# design.net
KiCad netlist of a schematic drawn in Altium Designer
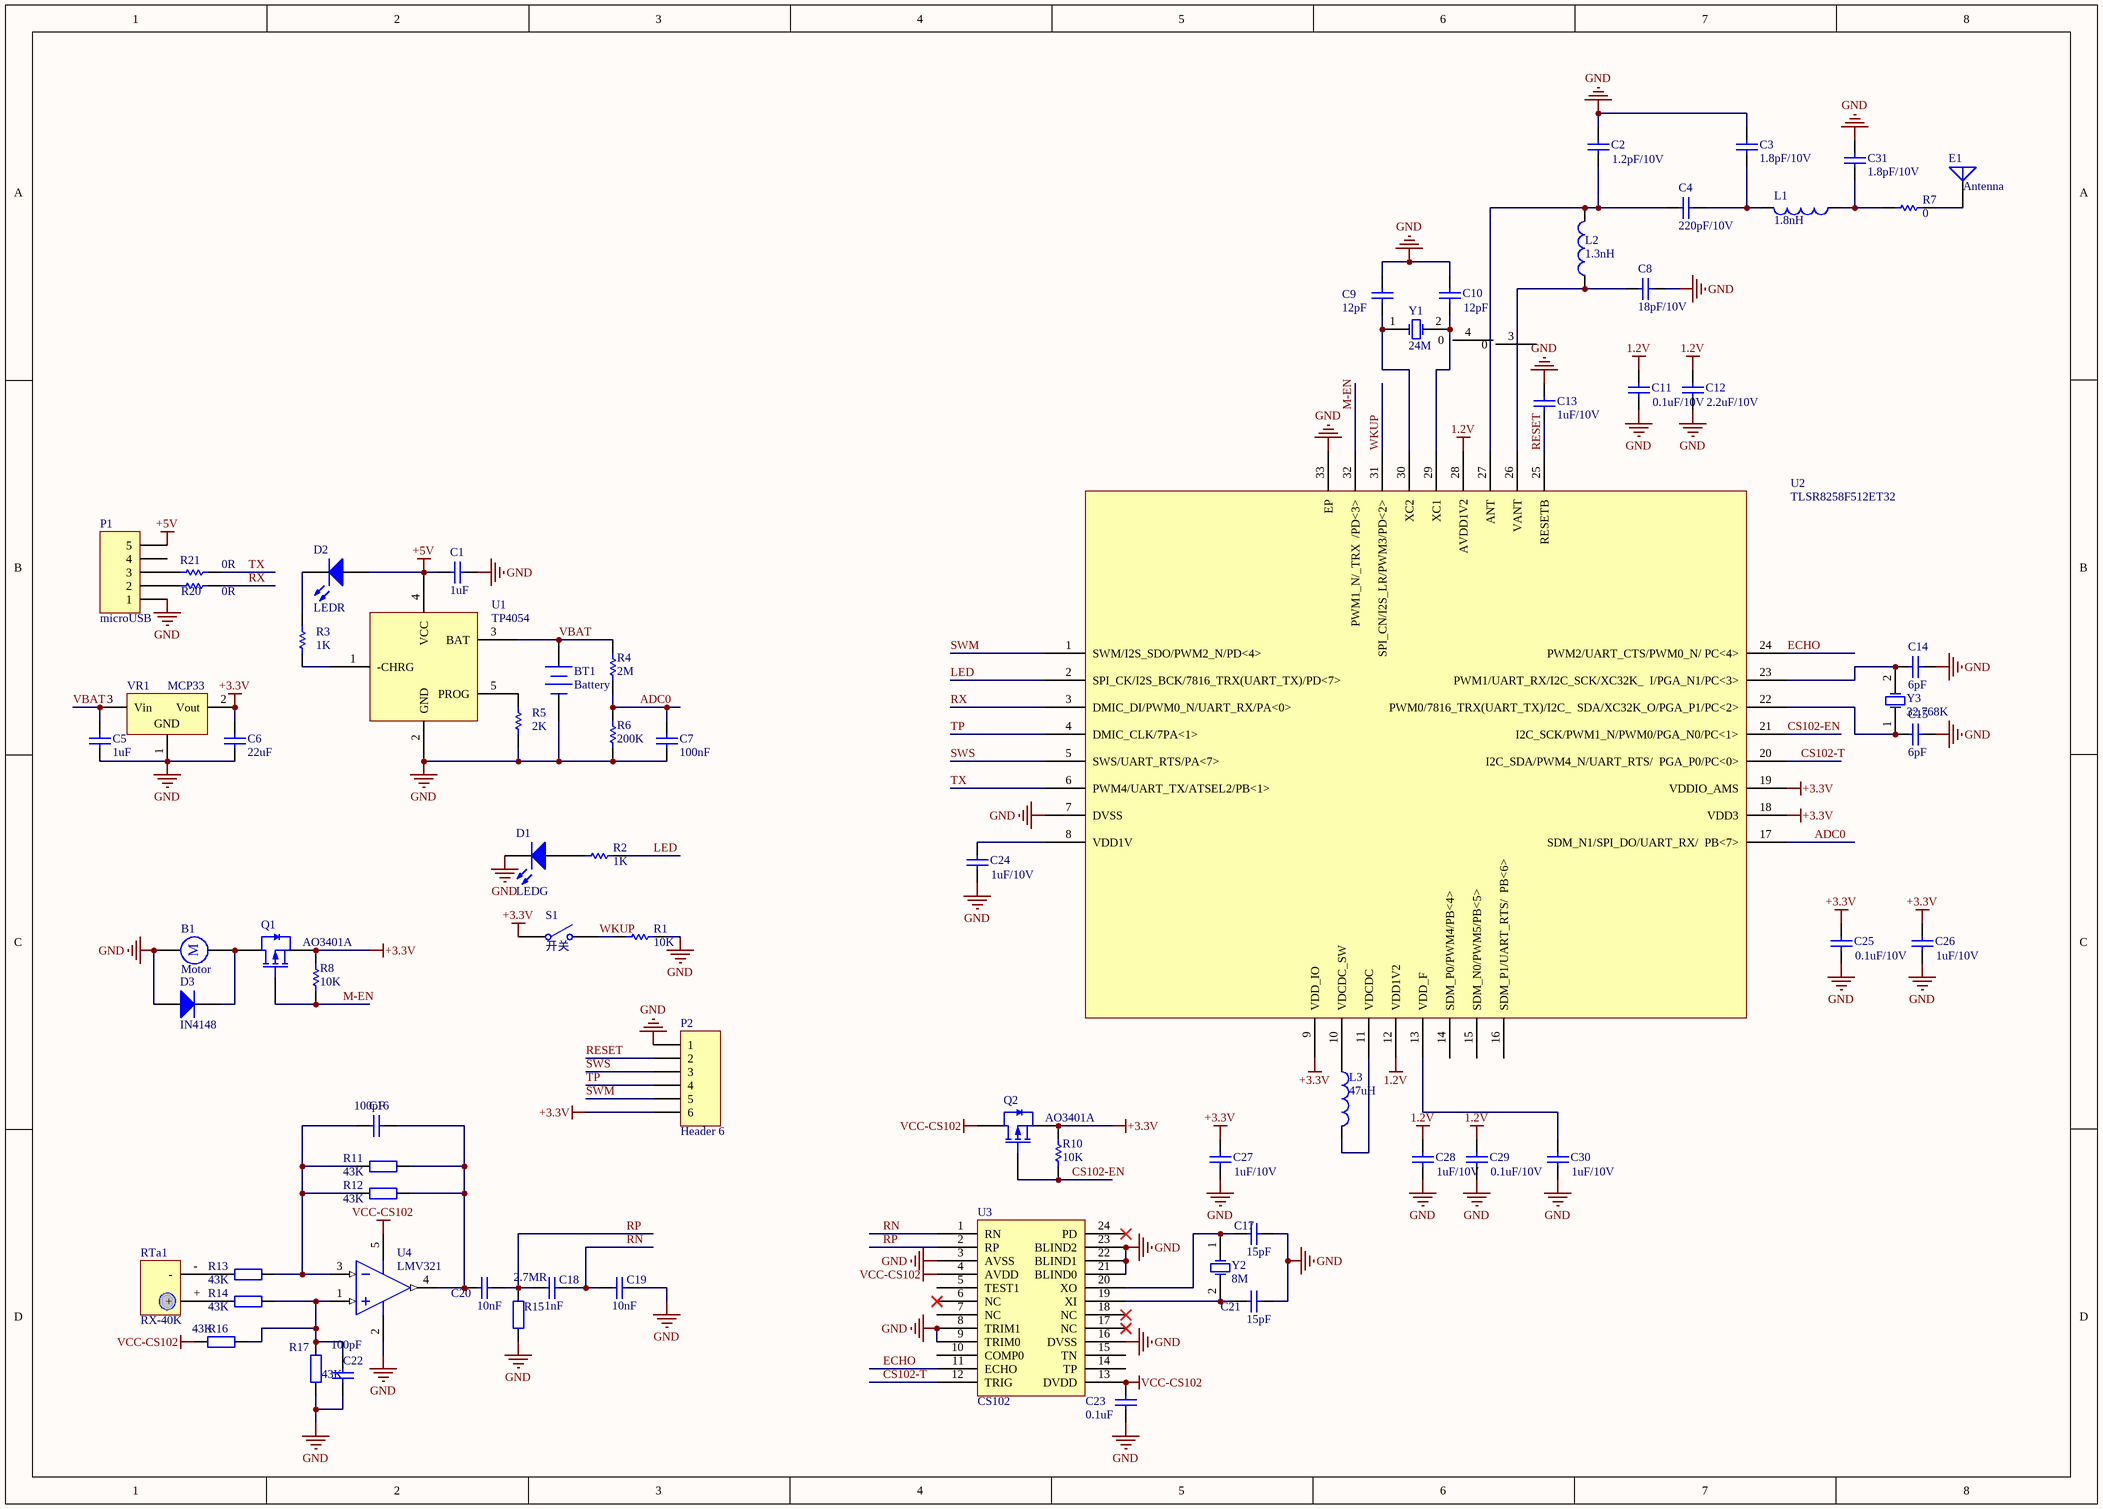
[diagram p0: 接收端原理图.SchDoc]

(export (version "E")
  (design (tool "Eeschema 10.0.6"))
  (components
    (comp (ref "B1")
      (value "Motor")
      (footprint "MOTO-40*44*114 - 3D")
      (description "Motor, General Kind")
      (fields (field (name "PUBLISHER") "Altium Limited"))
      (libsource (lib "Miscellaneous Devices") (part "Motor"))
    )
    (comp (ref "BT1")
      (value "Battery")
      (footprint "BT")
      (description "Multicell Battery")
      (fields (field (name "PUBLISHER") "Altium Limited"))
      (libsource (lib "Miscellaneous Devices") (part "Battery"))
    )
    (comp (ref "C1")
      (value "1uF")
      (description "Capacitor")
      (fields (field (name "PUBLISHER") "Altium Limited"))
      (libsource (lib "Miscellaneous Devices") (part "Cap"))
    )
    (comp (ref "C2")
      (value "1.2pF/10V")
      (footprint "0402")
      (description "Capacitor")
      (fields (field (name "PUBLISHER") "Altium Limited"))
      (libsource (lib "Miscellaneous Devices") (part "Cap"))
    )
    (comp (ref "C3")
      (value "1.8pF/10V")
      (footprint "0402")
      (description "Capacitor")
      (fields (field (name "PUBLISHER") "Altium Limited"))
      (libsource (lib "Miscellaneous Devices") (part "Cap"))
    )
    (comp (ref "C4")
      (value "220pF/10V")
      (footprint "0402")
      (description "Capacitor")
      (fields (field (name "PUBLISHER") "Altium Limited"))
      (libsource (lib "Miscellaneous Devices") (part "Cap"))
    )
    (comp (ref "C5")
      (value "1uF")
      (description "Capacitor")
      (fields (field (name "PUBLISHER") "Altium Limited"))
      (libsource (lib "Miscellaneous Devices") (part "Cap"))
    )
    (comp (ref "C6")
      (value "22uF")
      (description "Capacitor")
      (fields (field (name "PUBLISHER") "Altium Limited"))
      (libsource (lib "Miscellaneous Devices") (part "Cap"))
    )
    (comp (ref "C7")
      (value "100nF")
      (description "Capacitor")
      (fields (field (name "PUBLISHER") "Altium Limited"))
      (libsource (lib "Miscellaneous Devices") (part "Cap"))
    )
    (comp (ref "C8")
      (value "18pF/10V")
      (footprint "0402")
      (description "Capacitor")
      (fields (field (name "PUBLISHER") "Altium Limited"))
      (libsource (lib "Miscellaneous Devices") (part "Cap"))
    )
    (comp (ref "C9")
      (value "12pF")
      (footprint "0402")
      (description "Capacitor")
      (fields (field (name "PUBLISHER") "Altium Limited"))
      (libsource (lib "Miscellaneous Devices") (part "Cap"))
    )
    (comp (ref "C10")
      (value "12pF")
      (footprint "0402")
      (description "Capacitor")
      (fields (field (name "PUBLISHER") "Altium Limited"))
      (libsource (lib "Miscellaneous Devices") (part "Cap"))
    )
    (comp (ref "C11")
      (value "0.1uF/10V")
      (footprint "0402")
      (description "Capacitor")
      (fields (field (name "PUBLISHER") "Altium Limited"))
      (libsource (lib "Miscellaneous Devices") (part "Cap"))
    )
    (comp (ref "C12")
      (value "2.2uF/10V")
      (footprint "0402")
      (description "Capacitor")
      (fields (field (name "PUBLISHER") "Altium Limited"))
      (libsource (lib "Miscellaneous Devices") (part "Cap"))
    )
    (comp (ref "C13")
      (value "1uF/10V")
      (footprint "0402")
      (description "Capacitor")
      (fields (field (name "PUBLISHER") "Altium Limited"))
      (libsource (lib "Miscellaneous Devices") (part "Cap"))
    )
    (comp (ref "C14")
      (value "6pF")
      (footprint "0402")
      (description "Capacitor")
      (fields (field (name "PUBLISHER") "Altium Limited"))
      (libsource (lib "Miscellaneous Devices") (part "Cap"))
    )
    (comp (ref "C15")
      (value "6pF")
      (footprint "0402")
      (description "Capacitor")
      (fields (field (name "PUBLISHER") "Altium Limited"))
      (libsource (lib "Miscellaneous Devices") (part "Cap"))
    )
    (comp (ref "C16")
      (value "100pF")
      (footprint "0402")
      (description "Capacitor")
      (fields (field (name "PUBLISHER") "Altium Limited"))
      (libsource (lib "Miscellaneous Devices") (part "Cap"))
    )
    (comp (ref "C17")
      (value "15pF")
      (footprint "0402")
      (description "Capacitor")
      (fields (field (name "PUBLISHER") "Altium Limited"))
      (libsource (lib "Miscellaneous Devices") (part "Cap"))
    )
    (comp (ref "C18")
      (value "1nF")
      (footprint "0402")
      (description "Capacitor")
      (fields (field (name "PUBLISHER") "Altium Limited"))
      (libsource (lib "Miscellaneous Devices") (part "Cap"))
    )
    (comp (ref "C19")
      (value "10nF")
      (footprint "0402")
      (description "Capacitor")
      (fields (field (name "PUBLISHER") "Altium Limited"))
      (libsource (lib "Miscellaneous Devices") (part "Cap"))
    )
    (comp (ref "C20")
      (value "10nF")
      (footprint "0402")
      (description "Capacitor")
      (fields (field (name "PUBLISHER") "Altium Limited"))
      (libsource (lib "Miscellaneous Devices") (part "Cap"))
    )
    (comp (ref "C21")
      (value "15pF")
      (footprint "0402")
      (description "Capacitor")
      (fields (field (name "PUBLISHER") "Altium Limited"))
      (libsource (lib "Miscellaneous Devices") (part "Cap"))
    )
    (comp (ref "C22")
      (value "100pF")
      (footprint "0402")
      (description "Capacitor")
      (fields (field (name "PUBLISHER") "Altium Limited"))
      (libsource (lib "Miscellaneous Devices") (part "Cap"))
    )
    (comp (ref "C23")
      (value "0.1uF")
      (description "Capacitor")
      (fields (field (name "PUBLISHER") "Altium Limited"))
      (libsource (lib "Miscellaneous Devices") (part "Cap"))
    )
    (comp (ref "C24")
      (value "1uF/10V")
      (footprint "0402")
      (description "Capacitor")
      (fields (field (name "PUBLISHER") "Altium Limited"))
      (libsource (lib "Miscellaneous Devices") (part "Cap"))
    )
    (comp (ref "C25")
      (value "0.1uF/10V")
      (footprint "0402")
      (description "Capacitor")
      (fields (field (name "PUBLISHER") "Altium Limited"))
      (libsource (lib "Miscellaneous Devices") (part "Cap"))
    )
    (comp (ref "C26")
      (value "1uF/10V")
      (footprint "0402")
      (description "Capacitor")
      (fields (field (name "PUBLISHER") "Altium Limited"))
      (libsource (lib "Miscellaneous Devices") (part "Cap"))
    )
    (comp (ref "C27")
      (value "1uF/10V")
      (footprint "0402")
      (description "Capacitor")
      (fields (field (name "PUBLISHER") "Altium Limited"))
      (libsource (lib "Miscellaneous Devices") (part "Cap"))
    )
    (comp (ref "C28")
      (value "1uF/10V")
      (footprint "0402")
      (description "Capacitor")
      (fields (field (name "PUBLISHER") "Altium Limited"))
      (libsource (lib "Miscellaneous Devices") (part "Cap"))
    )
    (comp (ref "C29")
      (value "0.1uF/10V")
      (footprint "0402")
      (description "Capacitor")
      (fields (field (name "PUBLISHER") "Altium Limited"))
      (libsource (lib "Miscellaneous Devices") (part "Cap"))
    )
    (comp (ref "C30")
      (value "1uF/10V")
      (footprint "0402")
      (description "Capacitor")
      (fields (field (name "PUBLISHER") "Altium Limited"))
      (libsource (lib "Miscellaneous Devices") (part "Cap"))
    )
    (comp (ref "C31")
      (value "1.8pF/10V")
      (footprint "0402")
      (description "Capacitor")
      (fields (field (name "PUBLISHER") "Altium Limited"))
      (libsource (lib "Miscellaneous Devices") (part "Cap"))
    )
    (comp (ref "D1")
      (value "LEDG")
      (footprint "LED0603")
      (description "Typical INFRARED GaAs LED")
      (fields (field (name "PUBLISHER") "Altium Limited"))
      (libsource (lib "Miscellaneous Devices") (part "LED0"))
    )
    (comp (ref "D2")
      (value "LEDR")
      (footprint "LED0603")
      (description "Typical INFRARED GaAs LED")
      (fields (field (name "PUBLISHER") "Altium Limited"))
      (libsource (lib "Miscellaneous Devices") (part "LED0"))
    )
    (comp (ref "D3")
      (value "IN4148")
      (footprint "LED0603")
      (description "Default Diode")
      (fields (field (name "PUBLISHER") "Altium Limited"))
      (libsource (lib "Miscellaneous Devices") (part "Diode"))
    )
    (comp (ref "E1")
      (value "Antenna")
      (footprint "AN3216")
      (description "Generic Antenna")
      (fields (field (name "PUBLISHER") "Altium Limited"))
      (libsource (lib "Miscellaneous Devices") (part "Antenna"))
    )
    (comp (ref "L1")
      (value "1.8nH")
      (description "Inductor")
      (fields (field (name "PUBLISHER") "Altium Limited"))
      (libsource (lib "Miscellaneous Devices") (part "Inductor"))
    )
    (comp (ref "L2")
      (value "1.3nH")
      (description "Inductor")
      (fields (field (name "PUBLISHER") "Altium Limited"))
      (libsource (lib "Miscellaneous Devices") (part "Inductor"))
    )
    (comp (ref "L3")
      (value "47uH")
      (description "Inductor")
      (fields (field (name "PUBLISHER") "Altium Limited"))
      (libsource (lib "Miscellaneous Devices") (part "Inductor"))
    )
    (comp (ref "P1")
      (value "microUSB")
      (footprint "MICROUSB")
      (description "Header, 5-Pin")
      (fields (field (name "PUBLISHER") "Altium Limited"))
      (libsource (lib "Miscellaneous Connectors") (part "Header 5"))
    )
    (comp (ref "P2")
      (value "Header 6")
      (footprint "SIP6-1.27")
      (description "Header, 6-Pin")
      (fields (field (name "PUBLISHER") "Altium Limited"))
      (libsource (lib "Miscellaneous Connectors") (part "Header 6"))
    )
    (comp (ref "Q1")
      (value "AO3401A")
      (footprint "AO3401")
      (description "MOS(场效应管)")
      (libsource (lib "Miscellaneous Devices LC") (part "AO3401A P道沟 X13A15 SOT-23"))
    )
    (comp (ref "Q2")
      (value "AO3401A")
      (footprint "SOT23")
      (description "MOS(场效应管)")
      (libsource (lib "Miscellaneous Devices LC") (part "AO3401A P道沟 X13A15 SOT-23"))
    )
    (comp (ref "R1")
      (value "10K")
      (description "Resistor")
      (fields (field (name "PUBLISHER") "Altium Limited"))
      (libsource (lib "Miscellaneous Devices") (part "Res1"))
    )
    (comp (ref "R2")
      (value "1K")
      (description "Resistor")
      (fields (field (name "PUBLISHER") "Altium Limited"))
      (libsource (lib "Miscellaneous Devices") (part "Res1"))
    )
    (comp (ref "R3")
      (value "1K")
      (description "Resistor")
      (fields (field (name "PUBLISHER") "Altium Limited"))
      (libsource (lib "Miscellaneous Devices") (part "Res1"))
    )
    (comp (ref "R4")
      (value "2M")
      (description "Resistor")
      (fields (field (name "PUBLISHER") "Altium Limited"))
      (libsource (lib "Miscellaneous Devices") (part "Res1"))
    )
    (comp (ref "R5")
      (value "2K")
      (description "Resistor")
      (fields (field (name "PUBLISHER") "Altium Limited"))
      (libsource (lib "Miscellaneous Devices") (part "Res1"))
    )
    (comp (ref "R6")
      (value "200K")
      (description "Resistor")
      (fields (field (name "PUBLISHER") "Altium Limited"))
      (libsource (lib "Miscellaneous Devices") (part "Res1"))
    )
    (comp (ref "R7")
      (value "0")
      (description "Resistor")
      (fields (field (name "PUBLISHER") "Altium Limited"))
      (libsource (lib "Miscellaneous Devices") (part "Res1"))
    )
    (comp (ref "R8")
      (value "10K")
      (description "Resistor")
      (fields (field (name "PUBLISHER") "Altium Limited"))
      (libsource (lib "Miscellaneous Devices") (part "Res1"))
    )
    (comp (ref "R10")
      (value "10K")
      (description "Resistor")
      (fields (field (name "PUBLISHER") "Altium Limited"))
      (libsource (lib "Miscellaneous Devices") (part "Res1"))
    )
    (comp (ref "R11")
      (value "43K")
      (footprint "0402")
      (description "Resistor")
      (fields (field (name "PUBLISHER") "Altium Limited"))
      (libsource (lib "") (part "Res2_1"))
    )
    (comp (ref "R12")
      (value "43K")
      (footprint "0402")
      (description "Resistor")
      (fields (field (name "PUBLISHER") "Altium Limited"))
      (libsource (lib "") (part "Res2_1"))
    )
    (comp (ref "R13")
      (value "43K")
      (footprint "0402")
      (description "Resistor")
      (fields (field (name "PUBLISHER") "Altium Limited"))
      (libsource (lib "") (part "Res2_1"))
    )
    (comp (ref "R14")
      (value "43K")
      (footprint "0402")
      (description "Resistor")
      (fields (field (name "PUBLISHER") "Altium Limited"))
      (libsource (lib "") (part "Res2_1"))
    )
    (comp (ref "R15")
      (value "2.7MR")
      (footprint "0402")
      (description "Resistor")
      (fields (field (name "PUBLISHER") "Altium Limited"))
      (libsource (lib "Miscellaneous Devices") (part "Res2"))
    )
    (comp (ref "R16")
      (value "43K")
      (footprint "0402")
      (description "Resistor")
      (fields (field (name "PUBLISHER") "Altium Limited"))
      (libsource (lib "") (part "Res2_2"))
    )
    (comp (ref "R17")
      (value "43K")
      (footprint "0402")
      (description "Resistor")
      (fields (field (name "PUBLISHER") "Altium Limited"))
      (libsource (lib "Miscellaneous Devices") (part "Res2"))
    )
    (comp (ref "R20")
      (value "0R")
      (description "Resistor")
      (fields (field (name "PUBLISHER") "Altium Limited"))
      (libsource (lib "Miscellaneous Devices") (part "Res1"))
    )
    (comp (ref "R21")
      (value "0R")
      (description "Resistor")
      (fields (field (name "PUBLISHER") "Altium Limited"))
      (libsource (lib "Miscellaneous Devices") (part "Res1"))
    )
    (comp (ref "RTa1") (value "RX-40K") (footprint "US-10mm") (libsource (lib "USLib") (part "TC40K")))
    (comp (ref "S1")
      (value "开关")
      (footprint "SW3x6x5")
      (description "Single-Pole, Single-Throw Switch")
      (fields (field (name "PUBLISHER") "Altium Limited"))
      (libsource (lib "Miscellaneous Devices") (part "SW-SPST"))
    )
    (comp (ref "U1") (value "TP4054") (footprint "TP4054") (libsource (lib "Schlib1") (part "TP4054")))
    (comp (ref "U2")
      (value "TLSR8258F512ET32")
      (footprint "QFN-32")
      (libsource (lib "stm32") (part "TLSR8258F512ET32"))
    )
    (comp (ref "U3") (value "CS102") (footprint "TSSOP24") (libsource (lib "USLib") (part "CS100")))
    (comp (ref "U4")
      (value "LMV321")
      (footprint "MF05A_N")
      (description "General Purpose, Low Voltage, Rail-to-Rail Output Operational Amplifiers")
      (fields
        (field (name "PARTNUMBER") "LMV321M5")
        (field (name "MANUFACTURER") "National Semiconductor")
        (field (name "PUBLISHER") "Altium Limited")
      )
      (libsource (lib "NSC Amplifier") (part "LMV321M5"))
    )
    (comp (ref "VR1")
      (value "MCP33")
      (footprint "SOT23")
      (description "Voltage Regulator")
      (fields (field (name "PUBLISHER") "Altium Limited"))
      (libsource (lib "Miscellaneous Devices") (part "Volt Reg"))
    )
    (comp (ref "Y1")
      (value "24M")
      (footprint "XTAL4TN_3225")
      (description "Crystal Oscillator")
      (fields (field (name "PUBLISHER") "Altium Limited"))
      (libsource (lib "Miscellaneous Devices") (part "XTAL"))
    )
    (comp (ref "Y2")
      (value "8M")
      (footprint "5032")
      (description "Crystal Oscillator")
      (fields (field (name "PUBLISHER") "Altium Limited"))
      (libsource (lib "") (part "XTAL_1"))
    )
    (comp (ref "Y3")
      (value "32.768K")
      (footprint "S3215")
      (description "Crystal Oscillator")
      (fields (field (name "PUBLISHER") "Altium Limited"))
      (libsource (lib "") (part "XTAL_1"))
    )
  )
  (nets
    (net (code "1") (name "+3.3V") (class "Default")
      (node (ref "C25") (pin "2") (pinfunction "2_2") (pintype "passive"))
      (node (ref "C26") (pin "2") (pinfunction "2_2") (pintype "passive"))
      (node (ref "C27") (pin "2") (pinfunction "2_2") (pintype "passive"))
      (node (ref "C6") (pin "1") (pinfunction "1_1") (pintype "passive"))
      (node (ref "P2") (pin "6") (pinfunction "6_6") (pintype "passive"))
      (node (ref "Q1") (pin "2") (pinfunction "S_2") (pintype "passive"))
      (node (ref "Q2") (pin "2") (pinfunction "S_2") (pintype "passive"))
      (node (ref "R10") (pin "2") (pinfunction "2_2") (pintype "passive"))
      (node (ref "R8") (pin "2") (pinfunction "2_2") (pintype "passive"))
      (node (ref "S1") (pin "1") (pinfunction "COMMON_1") (pintype "passive"))
      (node (ref "U2") (pin "18") (pinfunction "VDD3_18") (pintype "passive"))
      (node (ref "U2") (pin "19") (pinfunction "VDDIO_AMS_19") (pintype "passive"))
      (node (ref "U2") (pin "9") (pinfunction "VDD_IO_9") (pintype "passive"))
      (node (ref "VR1") (pin "2") (pinfunction "Vout_2") (pintype "passive"))
    )
    (net (code "2") (name "+5V") (class "Default")
      (node (ref "C1") (pin "2") (pinfunction "2_2") (pintype "passive"))
      (node (ref "D2") (pin "1") (pinfunction "A_1") (pintype "passive"))
      (node (ref "P1") (pin "5") (pinfunction "5_5") (pintype "passive"))
      (node (ref "U1") (pin "4") (pinfunction "VCC_4") (pintype "passive"))
    )
    (net (code "3") (name "/ADC0") (class "Default")
      (node (ref "C7") (pin "2") (pinfunction "2_2") (pintype "passive"))
      (node (ref "R4") (pin "1") (pinfunction "1_1") (pintype "passive"))
      (node (ref "R6") (pin "2") (pinfunction "2_2") (pintype "passive"))
      (node (ref "U2") (pin "17") (pinfunction "SDM_N1/SPI_DO/UART_RX/__PB<7>_17") (pintype "passive"))
    )
    (net (code "4") (name "/CS102-EN") (class "Default")
      (node (ref "Q2") (pin "1") (pinfunction "G_1") (pintype "passive"))
      (node (ref "R10") (pin "1") (pinfunction "1_1") (pintype "passive"))
      (node (ref "U2") (pin "21") (pinfunction "I2C_SCK/PWM1_N/PWM0/PGA_N0/PC<1>_21") (pintype "passive"))
    )
    (net (code "5") (name "/CS102-T") (class "Default")
      (node (ref "U2") (pin "20") (pinfunction "I2C_SDA/PWM4_N/UART_RTS/__PGA_P0/PC<0>_20") (pintype "passive"))
      (node (ref "U3") (pin "12") (pinfunction "TRIG_12") (pintype "passive"))
    )
    (net (code "6") (name "/ECHO") (class "Default")
      (node (ref "U2") (pin "24") (pinfunction "PWM2/UART_CTS/PWM0_N/_PC<4>_24") (pintype "passive"))
      (node (ref "U3") (pin "11") (pinfunction "ECHO_11") (pintype "passive"))
    )
    (net (code "7") (name "/LED") (class "Default")
      (node (ref "R2") (pin "1") (pinfunction "1_1") (pintype "passive"))
      (node (ref "U2") (pin "2") (pinfunction "SPI_CK/I2S_BCK/7816_TRX(UART_TX)/PD<7>_2") (pintype "passive"))
    )
    (net (code "8") (name "/M-EN") (class "Default")
      (node (ref "Q1") (pin "1") (pinfunction "G_1") (pintype "passive"))
      (node (ref "R8") (pin "1") (pinfunction "1_1") (pintype "passive"))
      (node (ref "U2") (pin "32") (pinfunction "PWM1_N/_TRX__/PD<3>_32") (pintype "passive"))
    )
    (net (code "9") (name "/RESET") (class "Default")
      (node (ref "C13") (pin "2") (pinfunction "2_2") (pintype "passive"))
      (node (ref "P2") (pin "2") (pinfunction "2_2") (pintype "passive"))
      (node (ref "U2") (pin "25") (pinfunction "RESETB_25") (pintype "passive"))
    )
    (net (code "10") (name "/RN") (class "Default")
      (node (ref "C18") (pin "2") (pinfunction "2_2") (pintype "passive"))
      (node (ref "C19") (pin "1") (pinfunction "1_1") (pintype "passive"))
      (node (ref "U3") (pin "1") (pinfunction "RN_1") (pintype "passive"))
    )
    (net (code "11") (name "/RP") (class "Default")
      (node (ref "C18") (pin "1") (pinfunction "1_1") (pintype "passive"))
      (node (ref "C20") (pin "2") (pinfunction "2_2") (pintype "passive"))
      (node (ref "R15") (pin "2") (pinfunction "2_2") (pintype "passive"))
      (node (ref "U3") (pin "2") (pinfunction "RP_2") (pintype "passive"))
    )
    (net (code "12") (name "/RX") (class "Default")
      (node (ref "R20") (pin "1") (pinfunction "1_1") (pintype "passive"))
      (node (ref "U2") (pin "3") (pinfunction "DMIC_DI/PWM0_N/UART_RX/PA<0>_3") (pintype "passive"))
    )
    (net (code "13") (name "/SWM") (class "Default")
      (node (ref "P2") (pin "5") (pinfunction "5_5") (pintype "passive"))
      (node (ref "U2") (pin "1") (pinfunction "SWM/I2S_SDO/PWM2_N/PD<4>_1") (pintype "passive"))
    )
    (net (code "14") (name "/SWS") (class "Default")
      (node (ref "P2") (pin "3") (pinfunction "3_3") (pintype "passive"))
      (node (ref "U2") (pin "5") (pinfunction "SWS/UART_RTS/PA<7>_5") (pintype "passive"))
    )
    (net (code "15") (name "/TP") (class "Default")
      (node (ref "P2") (pin "4") (pinfunction "4_4") (pintype "passive"))
      (node (ref "U2") (pin "4") (pinfunction "DMIC_CLK/7PA<1>_4") (pintype "passive"))
    )
    (net (code "16") (name "/TX") (class "Default")
      (node (ref "R21") (pin "1") (pinfunction "1_1") (pintype "passive"))
      (node (ref "U2") (pin "6") (pinfunction "PWM4/UART_TX/ATSEL2/PB<1>_6") (pintype "passive"))
    )
    (net (code "17") (name "/VBAT") (class "Default")
      (node (ref "BT1") (pin "1") (pinfunction "+_1") (pintype "passive"))
      (node (ref "C5") (pin "1") (pinfunction "1_1") (pintype "passive"))
      (node (ref "R4") (pin "2") (pinfunction "2_2") (pintype "passive"))
      (node (ref "U1") (pin "3") (pinfunction "BAT_3") (pintype "passive"))
      (node (ref "VR1") (pin "3") (pinfunction "Vin_3") (pintype "passive"))
    )
    (net (code "18") (name "/WKUP") (class "Default")
      (node (ref "R1") (pin "2") (pinfunction "2_2") (pintype "passive"))
      (node (ref "S1") (pin "2") (pinfunction "NO_2") (pintype "passive"))
      (node (ref "U2") (pin "31") (pinfunction "SPI_CN/I2S_LR/PWM3/PD<2>_31") (pintype "passive"))
    )
    (net (code "19") (name "1.2V") (class "Default")
      (node (ref "C11") (pin "2") (pinfunction "2_2") (pintype "passive"))
      (node (ref "C12") (pin "2") (pinfunction "2_2") (pintype "passive"))
      (node (ref "C28") (pin "2") (pinfunction "2_2") (pintype "passive"))
      (node (ref "C29") (pin "2") (pinfunction "2_2") (pintype "passive"))
      (node (ref "U2") (pin "12") (pinfunction "VDD1V2_12") (pintype "passive"))
      (node (ref "U2") (pin "28") (pinfunction "AVDD1V2_28") (pintype "passive"))
    )
    (net (code "20") (name "GND") (class "Default")
      (node (ref "B1") (pin "1") (pinfunction "1_1") (pintype "passive"))
      (node (ref "BT1") (pin "2") (pinfunction "-_2") (pintype "passive"))
      (node (ref "C1") (pin "1") (pinfunction "1_1") (pintype "passive"))
      (node (ref "C10") (pin "2") (pinfunction "2_2") (pintype "passive"))
      (node (ref "C11") (pin "1") (pinfunction "1_1") (pintype "passive"))
      (node (ref "C12") (pin "1") (pinfunction "1_1") (pintype "passive"))
      (node (ref "C13") (pin "1") (pinfunction "1_1") (pintype "passive"))
      (node (ref "C14") (pin "1") (pinfunction "1_1") (pintype "passive"))
      (node (ref "C15") (pin "1") (pinfunction "1_1") (pintype "passive"))
      (node (ref "C17") (pin "2") (pinfunction "2_2") (pintype "passive"))
      (node (ref "C19") (pin "2") (pinfunction "2_2") (pintype "passive"))
      (node (ref "C2") (pin "2") (pinfunction "2_2") (pintype "passive"))
      (node (ref "C21") (pin "2") (pinfunction "2_2") (pintype "passive"))
      (node (ref "C22") (pin "1") (pinfunction "1_1") (pintype "passive"))
      (node (ref "C23") (pin "1") (pinfunction "1_1") (pintype "passive"))
      (node (ref "C24") (pin "1") (pinfunction "1_1") (pintype "passive"))
      (node (ref "C25") (pin "1") (pinfunction "1_1") (pintype "passive"))
      (node (ref "C26") (pin "1") (pinfunction "1_1") (pintype "passive"))
      (node (ref "C27") (pin "1") (pinfunction "1_1") (pintype "passive"))
      (node (ref "C28") (pin "1") (pinfunction "1_1") (pintype "passive"))
      (node (ref "C29") (pin "1") (pinfunction "1_1") (pintype "passive"))
      (node (ref "C3") (pin "1") (pinfunction "1_1") (pintype "passive"))
      (node (ref "C30") (pin "1") (pinfunction "1_1") (pintype "passive"))
      (node (ref "C31") (pin "1") (pinfunction "1_1") (pintype "passive"))
      (node (ref "C5") (pin "2") (pinfunction "2_2") (pintype "passive"))
      (node (ref "C6") (pin "2") (pinfunction "2_2") (pintype "passive"))
      (node (ref "C7") (pin "1") (pinfunction "1_1") (pintype "passive"))
      (node (ref "C8") (pin "1") (pinfunction "1_1") (pintype "passive"))
      (node (ref "C9") (pin "2") (pinfunction "2_2") (pintype "passive"))
      (node (ref "D1") (pin "2") (pinfunction "K_2") (pintype "passive"))
      (node (ref "D3") (pin "1") (pinfunction "A_1") (pintype "passive"))
      (node (ref "P1") (pin "1") (pinfunction "1_1") (pintype "passive"))
      (node (ref "P2") (pin "1") (pinfunction "1_1") (pintype "passive"))
      (node (ref "R1") (pin "1") (pinfunction "1_1") (pintype "passive"))
      (node (ref "R15") (pin "1") (pinfunction "1_1") (pintype "passive"))
      (node (ref "R17") (pin "1") (pinfunction "1_1") (pintype "passive"))
      (node (ref "R5") (pin "1") (pinfunction "1_1") (pintype "passive"))
      (node (ref "R6") (pin "1") (pinfunction "1_1") (pintype "passive"))
      (node (ref "U1") (pin "2") (pinfunction "GND_2") (pintype "passive"))
      (node (ref "U2") (pin "33") (pinfunction "EP_33") (pintype "passive"))
      (node (ref "U2") (pin "7") (pinfunction "DVSS_7") (pintype "passive"))
      (node (ref "U3") (pin "16") (pinfunction "DVSS_16") (pintype "passive"))
      (node (ref "U3") (pin "21") (pinfunction "BLIND0_21") (pintype "passive"))
      (node (ref "U3") (pin "22") (pinfunction "BLIND1_22") (pintype "passive"))
      (node (ref "U3") (pin "23") (pinfunction "BLIND2_23") (pintype "passive"))
      (node (ref "U3") (pin "3") (pinfunction "AVSS_3") (pintype "passive"))
      (node (ref "U3") (pin "8") (pinfunction "TRIM1_8") (pintype "passive"))
      (node (ref "U3") (pin "9") (pinfunction "TRIM0_9") (pintype "passive"))
      (node (ref "U4") (pin "2") (pinfunction "V-_2") (pintype "power_in"))
      (node (ref "VR1") (pin "1") (pinfunction "GND_1") (pintype "passive"))
    )
    (net (code "21") (name "Net-(C3-Pad2)") (class "Default")
      (node (ref "C3") (pin "2") (pinfunction "2_2") (pintype "passive"))
      (node (ref "C4") (pin "1") (pinfunction "1_1") (pintype "passive"))
      (node (ref "L1") (pin "2") (pinfunction "2_2") (pintype "passive"))
    )
    (net (code "22") (name "Net-(C31-Pad2)") (class "Default")
      (node (ref "C31") (pin "2") (pinfunction "2_2") (pintype "passive"))
      (node (ref "L1") (pin "1") (pinfunction "1_1") (pintype "passive"))
      (node (ref "R7") (pin "2") (pinfunction "2_2") (pintype "passive"))
    )
    (net (code "23") (name "Net-(D1-A)") (class "Default")
      (node (ref "D1") (pin "1") (pinfunction "A_1") (pintype "passive"))
      (node (ref "R2") (pin "2") (pinfunction "2_2") (pintype "passive"))
    )
    (net (code "24") (name "Net-(D2-K)") (class "Default")
      (node (ref "D2") (pin "2") (pinfunction "K_2") (pintype "passive"))
      (node (ref "R3") (pin "2") (pinfunction "2_2") (pintype "passive"))
    )
    (net (code "25") (name "Net-(D3-K)") (class "Default")
      (node (ref "B1") (pin "2") (pinfunction "2_2") (pintype "passive"))
      (node (ref "D3") (pin "2") (pinfunction "K_2") (pintype "passive"))
      (node (ref "Q1") (pin "3") (pinfunction "D_3") (pintype "passive"))
    )
    (net (code "26") (name "Net-(E1-A)") (class "Default")
      (node (ref "E1") (pin "1") (pinfunction "A_1") (pintype "passive"))
      (node (ref "R7") (pin "1") (pinfunction "1_1") (pintype "passive"))
    )
    (net (code "27") (name "Net-(P1-Pad2)") (class "Default")
      (node (ref "P1") (pin "2") (pinfunction "2_2") (pintype "passive"))
      (node (ref "R20") (pin "2") (pinfunction "2_2") (pintype "passive"))
    )
    (net (code "28") (name "Net-(P1-Pad3)") (class "Default")
      (node (ref "P1") (pin "3") (pinfunction "3_3") (pintype "passive"))
      (node (ref "R21") (pin "2") (pinfunction "2_2") (pintype "passive"))
    )
    (net (code "29") (name "Net-(R13-Pad1)") (class "Default")
      (node (ref "R13") (pin "1") (pinfunction "1_1") (pintype "passive"))
      (node (ref "RTa1") (pin "-") (pinfunction "-_-") (pintype "passive"))
    )
    (net (code "30") (name "Net-(R14-Pad1)") (class "Default")
      (node (ref "R14") (pin "1") (pinfunction "1_1") (pintype "passive"))
      (node (ref "RTa1") (pin "+") (pinfunction "+_+") (pintype "passive"))
    )
    (net (code "31") (name "Net-(U1--CHRG)") (class "Default")
      (node (ref "R3") (pin "1") (pinfunction "1_1") (pintype "passive"))
      (node (ref "U1") (pin "1") (pinfunction "-CHRG_1") (pintype "passive"))
    )
    (net (code "32") (name "Net-(U1-PROG)") (class "Default")
      (node (ref "R5") (pin "2") (pinfunction "2_2") (pintype "passive"))
      (node (ref "U1") (pin "5") (pinfunction "PROG_5") (pintype "passive"))
    )
    (net (code "33") (name "Net-(U2-ANT)") (class "Default")
      (node (ref "C2") (pin "1") (pinfunction "1_1") (pintype "passive"))
      (node (ref "C4") (pin "2") (pinfunction "2_2") (pintype "passive"))
      (node (ref "L2") (pin "2") (pinfunction "2_2") (pintype "passive"))
      (node (ref "U2") (pin "27") (pinfunction "ANT_27") (pintype "passive"))
    )
    (net (code "34") (name "Net-(U2-PWM0{slash}7816_TRX(UART_TX){slash}I2C___SDA{slash}XC32K_O{slash}PGA_P1{slash}PC<2>)") (class "Default")
      (node (ref "C15") (pin "2") (pinfunction "2_2") (pintype "passive"))
      (node (ref "U2") (pin "22") (pinfunction "PWM0/7816_TRX(UART_TX)/I2C___SDA/XC32K_O/PGA_P1/PC<2>_22") (pintype "passive"))
      (node (ref "Y3") (pin "1") (pinfunction "OSC1_1") (pintype "passive"))
    )
    (net (code "35") (name "Net-(U2-PWM1{slash}UART_RX{slash}I2C_SCK{slash}XC32K___I{slash}PGA_N1{slash}PC<3>)") (class "Default")
      (node (ref "C14") (pin "2") (pinfunction "2_2") (pintype "passive"))
      (node (ref "U2") (pin "23") (pinfunction "PWM1/UART_RX/I2C_SCK/XC32K___I/PGA_N1/PC<3>_23") (pintype "passive"))
      (node (ref "Y3") (pin "2") (pinfunction "OSC2_2") (pintype "passive"))
    )
    (net (code "36") (name "Net-(U2-VANT)") (class "Default")
      (node (ref "C8") (pin "2") (pinfunction "2_2") (pintype "passive"))
      (node (ref "L2") (pin "1") (pinfunction "1_1") (pintype "passive"))
      (node (ref "U2") (pin "26") (pinfunction "VANT_26") (pintype "passive"))
    )
    (net (code "37") (name "Net-(U2-VDCDC)") (class "Default")
      (node (ref "L3") (pin "2") (pinfunction "2_2") (pintype "passive"))
      (node (ref "U2") (pin "11") (pinfunction "VDCDC_11") (pintype "passive"))
    )
    (net (code "38") (name "Net-(U2-VDCDC_SW)") (class "Default")
      (node (ref "L3") (pin "1") (pinfunction "1_1") (pintype "passive"))
      (node (ref "U2") (pin "10") (pinfunction "VDCDC_SW_10") (pintype "passive"))
    )
    (net (code "39") (name "Net-(U2-VDD1V)") (class "Default")
      (node (ref "C24") (pin "2") (pinfunction "2_2") (pintype "passive"))
      (node (ref "U2") (pin "8") (pinfunction "VDD1V_8") (pintype "passive"))
    )
    (net (code "40") (name "Net-(U2-VDD_F)") (class "Default")
      (node (ref "C30") (pin "2") (pinfunction "2_2") (pintype "passive"))
      (node (ref "U2") (pin "13") (pinfunction "VDD_F_13") (pintype "passive"))
    )
    (net (code "41") (name "Net-(U2-XC1)") (class "Default")
      (node (ref "C10") (pin "1") (pinfunction "1_1") (pintype "passive"))
      (node (ref "U2") (pin "29") (pinfunction "XC1_29") (pintype "passive"))
      (node (ref "Y1") (pin "2") (pinfunction "OSC2_2") (pintype "passive"))
    )
    (net (code "42") (name "Net-(U2-XC2)") (class "Default")
      (node (ref "C9") (pin "1") (pinfunction "1_1") (pintype "passive"))
      (node (ref "U2") (pin "30") (pinfunction "XC2_30") (pintype "passive"))
      (node (ref "Y1") (pin "1") (pinfunction "OSC1_1") (pintype "passive"))
    )
    (net (code "43") (name "Net-(U3-XI)") (class "Default")
      (node (ref "C21") (pin "1") (pinfunction "1_1") (pintype "passive"))
      (node (ref "U3") (pin "19") (pinfunction "XI_19") (pintype "passive"))
      (node (ref "Y2") (pin "2") (pinfunction "OSC2_2") (pintype "passive"))
    )
    (net (code "44") (name "Net-(U3-XO)") (class "Default")
      (node (ref "C17") (pin "1") (pinfunction "1_1") (pintype "passive"))
      (node (ref "U3") (pin "20") (pinfunction "XO_20") (pintype "passive"))
      (node (ref "Y2") (pin "1") (pinfunction "OSC1_1") (pintype "passive"))
    )
    (net (code "45") (name "Net-(U4-IN+)") (class "Default")
      (node (ref "C22") (pin "2") (pinfunction "2_2") (pintype "passive"))
      (node (ref "R14") (pin "2") (pinfunction "2_2") (pintype "passive"))
      (node (ref "R16") (pin "1") (pinfunction "1_1") (pintype "passive"))
      (node (ref "R17") (pin "2") (pinfunction "2_2") (pintype "passive"))
      (node (ref "U4") (pin "1") (pinfunction "IN+_1") (pintype "input"))
    )
    (net (code "46") (name "Net-(U4-IN-)") (class "Default")
      (node (ref "C16") (pin "2") (pinfunction "2_2") (pintype "passive"))
      (node (ref "R11") (pin "1") (pinfunction "1_1") (pintype "passive"))
      (node (ref "R12") (pin "1") (pinfunction "1_1") (pintype "passive"))
      (node (ref "R13") (pin "2") (pinfunction "2_2") (pintype "passive"))
      (node (ref "U4") (pin "3") (pinfunction "IN-_3") (pintype "input"))
    )
    (net (code "47") (name "Net-(U4-OUT)") (class "Default")
      (node (ref "C16") (pin "1") (pinfunction "1_1") (pintype "passive"))
      (node (ref "C20") (pin "1") (pinfunction "1_1") (pintype "passive"))
      (node (ref "R11") (pin "2") (pinfunction "2_2") (pintype "passive"))
      (node (ref "R12") (pin "2") (pinfunction "2_2") (pintype "passive"))
      (node (ref "U4") (pin "4") (pinfunction "OUT_4") (pintype "output"))
    )
    (net (code "48") (name "VCC-CS102") (class "Default")
      (node (ref "C23") (pin "2") (pinfunction "2_2") (pintype "passive"))
      (node (ref "Q2") (pin "3") (pinfunction "D_3") (pintype "passive"))
      (node (ref "R16") (pin "2") (pinfunction "2_2") (pintype "passive"))
      (node (ref "U3") (pin "13") (pinfunction "DVDD_13") (pintype "passive"))
      (node (ref "U3") (pin "4") (pinfunction "AVDD_4") (pintype "passive"))
      (node (ref "U4") (pin "5") (pinfunction "V+_5") (pintype "power_in"))
    )
    (net (code "49") (name "unconnected-(P1-Pad4)") (class "Default")
      (node (ref "P1") (pin "4") (pinfunction "4_4") (pintype "passive"))
    )
    (net (code "50") (name "unconnected-(U2-SDM_N0{slash}PWM5{slash}PB<5>-Pad15)") (class "Default")
      (node (ref "U2") (pin "15") (pinfunction "SDM_N0/PWM5/PB<5>_15") (pintype "passive"))
    )
    (net (code "51") (name "unconnected-(U2-SDM_P0{slash}PWM4{slash}PB<4>-Pad14)") (class "Default")
      (node (ref "U2") (pin "14") (pinfunction "SDM_P0/PWM4/PB<4>_14") (pintype "passive"))
    )
    (net (code "52") (name "unconnected-(U2-SDM_P1{slash}UART_RTS{slash}__PB<6>-Pad16)") (class "Default")
      (node (ref "U2") (pin "16") (pinfunction "SDM_P1/UART_RTS/__PB<6>_16") (pintype "passive"))
    )
    (net (code "53") (name "unconnected-(U3-COMP0-Pad10)") (class "Default")
      (node (ref "U3") (pin "10") (pinfunction "COMP0_10") (pintype "passive"))
    )
    (net (code "54") (name "unconnected-(U3-NC-Pad6)") (class "Default")
      (node (ref "U3") (pin "6") (pinfunction "NC_6") (pintype "passive+no_connect"))
    )
    (net (code "55") (name "unconnected-(U3-NC-Pad7)") (class "Default")
      (node (ref "U3") (pin "7") (pinfunction "NC_7") (pintype "passive"))
    )
    (net (code "56") (name "unconnected-(U3-NC-Pad17)") (class "Default")
      (node (ref "U3") (pin "17") (pinfunction "NC_17") (pintype "passive+no_connect"))
    )
    (net (code "57") (name "unconnected-(U3-NC-Pad18)") (class "Default")
      (node (ref "U3") (pin "18") (pinfunction "NC_18") (pintype "passive+no_connect"))
    )
    (net (code "58") (name "unconnected-(U3-PD-Pad24)") (class "Default")
      (node (ref "U3") (pin "24") (pinfunction "PD_24") (pintype "passive+no_connect"))
    )
    (net (code "59") (name "unconnected-(U3-TEST1-Pad5)") (class "Default")
      (node (ref "U3") (pin "5") (pinfunction "TEST1_5") (pintype "passive"))
    )
    (net (code "60") (name "unconnected-(U3-TN-Pad15)") (class "Default")
      (node (ref "U3") (pin "15") (pinfunction "TN_15") (pintype "passive"))
    )
    (net (code "61") (name "unconnected-(U3-TP-Pad14)") (class "Default")
      (node (ref "U3") (pin "14") (pinfunction "TP_14") (pintype "passive"))
    )
    (net (code "62") (name "unconnected-(Y1-0-Pad3)") (class "Default")
      (node (ref "Y1") (pin "3") (pinfunction "0_3") (pintype "passive"))
    )
    (net (code "63") (name "unconnected-(Y1-0-Pad4)") (class "Default")
      (node (ref "Y1") (pin "4") (pinfunction "0_4") (pintype "passive"))
    )
  )
)
